# G_R.net
KiCad netlist of a schematic drawn in Altium Designer
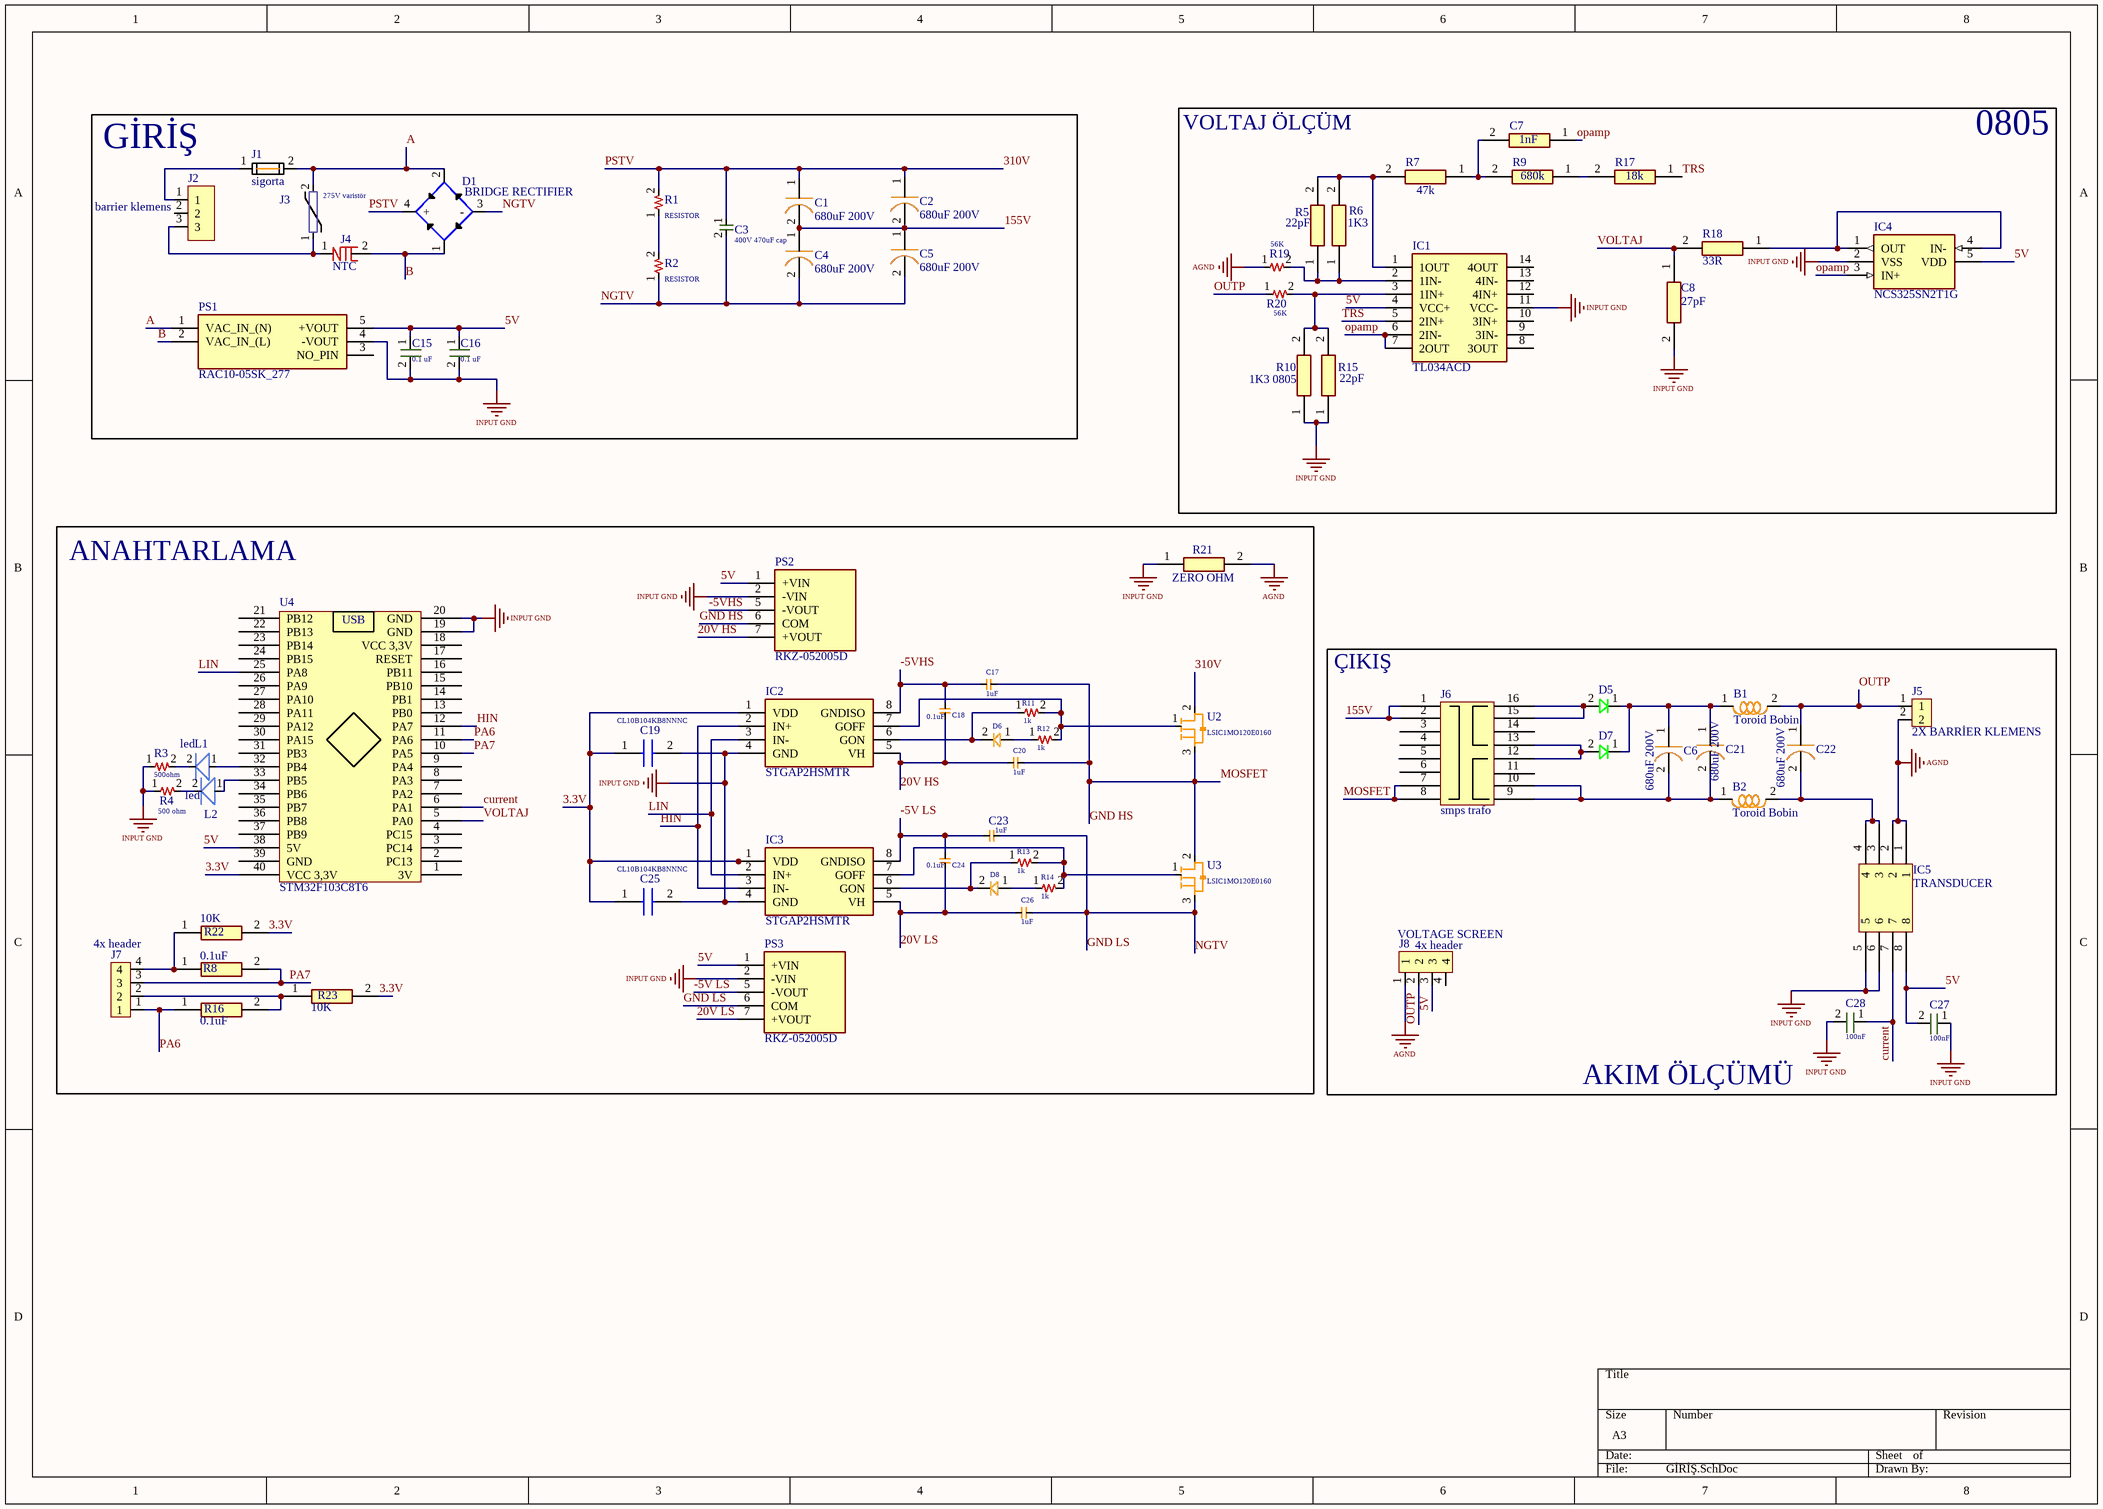
[diagram p0: GİRİŞ.SchDoc]

(export (version "E")
  (design (tool "Eeschema 10.0.6"))
  (components
    (comp (ref "B1")
      (value "Toroid Bobin")
      (footprint "toroid bobin")
      (libsource (lib "Schlib2") (part "Toroid Bobin"))
    )
    (comp (ref "B2")
      (value "Toroid Bobin")
      (footprint "toroid bobin")
      (libsource (lib "Schlib2") (part "Toroid Bobin"))
    )
    (comp (ref "C1")
      (value "680uF 200V")
      (footprint "200v 680uF CAPACITOR")
      (description "CAPACITOR")
      (libsource (lib "Schlib2") (part "680uF 200V"))
    )
    (comp (ref "C2")
      (value "680uF 200V")
      (footprint "200v 680uF CAPACITOR")
      (description "CAPACITOR")
      (libsource (lib "Schlib2") (part "680uF 200V"))
    )
    (comp (ref "C3")
      (value "400V 470uF cap")
      (footprint "400V 470uF")
      (description "470 uF")
      (libsource (lib "Schlib2") (part "400V 470uF cap"))
    )
    (comp (ref "C4")
      (value "680uF 200V")
      (footprint "200v 680uF CAPACITOR")
      (description "CAPACITOR")
      (libsource (lib "Schlib2") (part "680uF 200V"))
    )
    (comp (ref "C5")
      (value "680uF 200V")
      (footprint "200v 680uF CAPACITOR")
      (description "CAPACITOR")
      (libsource (lib "Schlib2") (part "680uF 200V"))
    )
    (comp (ref "C6")
      (value "680uF 200V")
      (footprint "200v 680uF CAPACITOR")
      (description "CAPACITOR")
      (libsource (lib "Schlib2") (part "680uF 200V"))
    )
    (comp (ref "C7")
      (value "1nF")
      (footprint "PcbLib3:RESC2012X65N")
      (description "Resistor")
      (fields
        (field (name "MANUFACTURER_PART_NUMBER") "CPF0805B100RE1")
        (field (name "MOUSER PART NUMBER") "279-CPF0805B100RE1")
      )
      (libsource (lib "") (part "CPF0805B100RE1_3"))
    )
    (comp (ref "C8")
      (value "27pF")
      (footprint "PcbLib3:RESC2012X65N")
      (description "Resistor")
      (fields
        (field (name "MANUFACTURER_PART_NUMBER") "CPF0805B100RE1")
        (field (name "MOUSER PART NUMBER") "279-CPF0805B100RE1")
      )
      (libsource (lib "") (part "CPF0805B100RE1_2"))
    )
    (comp (ref "C15")
      (value "0.1 uF")
      (footprint "0.1 uF mercimek kapasitör")
      (description "CAPACITOR")
      (libsource (lib "Schlib2") (part "0.1 uF mercimek kapasitör"))
    )
    (comp (ref "C16")
      (value "0.1 uF")
      (footprint "0.1 uF mercimek kapasitör")
      (description "CAPACITOR")
      (libsource (lib "Schlib2") (part "0.1 uF mercimek kapasitör"))
    )
    (comp (ref "C17")
      (value "1uF")
      (footprint "KUTU KAPASİTÖR 1uF")
      (libsource (lib "Schlib2") (part "KUTU KAPASİTÖR 1uF"))
    )
    (comp (ref "C18")
      (value "0.1uF")
      (footprint "KUTU KAPASİTÖR 1uF")
      (description "1uF")
      (libsource (lib "Schlib2") (part "KUTU KAPASİTÖR 1uF"))
    )
    (comp (ref "C19")
      (value "CL10B104KB8NNNC")
      (footprint "PcbLib2:CAPC1608X90N")
      (description "Capacitor")
      (fields (field (name "MOUSER PART NUMBER") "187-CL10B104KB8NNNC"))
      (libsource (lib "*") (part "CL10B104KB8NNNC"))
    )
    (comp (ref "C20")
      (value "1uF")
      (footprint "KUTU KAPASİTÖR 1uF")
      (libsource (lib "Schlib2") (part "KUTU KAPASİTÖR 1uF"))
    )
    (comp (ref "C21")
      (value "680uF 200V")
      (footprint "200v 680uF CAPACITOR")
      (description "CAPACITOR")
      (libsource (lib "Schlib2") (part "680uF 200V"))
    )
    (comp (ref "C22")
      (value "680uF 200V")
      (footprint "200v 680uF CAPACITOR")
      (description "CAPACITOR")
      (libsource (lib "Schlib2") (part "680uF 200V"))
    )
    (comp (ref "C23")
      (value "1uF")
      (footprint "KUTU KAPASİTÖR 1uF")
      (libsource (lib "Schlib2") (part "KUTU KAPASİTÖR 1uF"))
    )
    (comp (ref "C24")
      (value "0.1uF")
      (footprint "KUTU KAPASİTÖR 1uF")
      (description "1uF")
      (libsource (lib "Schlib2") (part "KUTU KAPASİTÖR 1uF"))
    )
    (comp (ref "C25")
      (value "CL10B104KB8NNNC")
      (footprint "PcbLib2:CAPC1608X90N")
      (description "Capacitor")
      (fields (field (name "MOUSER PART NUMBER") "187-CL10B104KB8NNNC"))
      (libsource (lib "*") (part "CL10B104KB8NNNC"))
    )
    (comp (ref "C26")
      (value "1uF")
      (footprint "KUTU KAPASİTÖR 1uF")
      (libsource (lib "Schlib2") (part "KUTU KAPASİTÖR 1uF"))
    )
    (comp (ref "C27")
      (value "100nF")
      (footprint "0.1 uF mercimek kapasitör")
      (description "CAPACITOR")
      (libsource (lib "Schlib2") (part "0.1 uF mercimek kapasitör"))
    )
    (comp (ref "C28")
      (value "100nF")
      (footprint "0.1 uF mercimek kapasitör")
      (description "CAPACITOR")
      (libsource (lib "Schlib2") (part "0.1 uF mercimek kapasitör"))
    )
    (comp (ref "D1")
      (value "BRIDGE RECTIFIER")
      (footprint "RECTIFIER")
      (description "RECTIFIER")
      (libsource (lib "Schlib2") (part "BRIDGE RECTIFIER"))
    )
    (comp (ref "D5")
      (value "MUR1560 DIODE")
      (footprint "MUR1560 FAST DIODE")
      (description "DIODE")
      (libsource (lib "Schlib2") (part "MUR1560 DIODE"))
    )
    (comp (ref "D6")
      (value "SF-26 DIODE")
      (footprint "SF-26 DIODE")
      (description "DIODE")
      (libsource (lib "Schlib2") (part "SF-26 DIODE"))
    )
    (comp (ref "D7")
      (value "MUR1560 DIODE")
      (footprint "MUR1560 FAST DIODE")
      (description "DIODE")
      (libsource (lib "Schlib2") (part "MUR1560 DIODE"))
    )
    (comp (ref "D8")
      (value "SF-26 DIODE")
      (footprint "SF-26 DIODE")
      (description "DIODE")
      (libsource (lib "Schlib2") (part "SF-26 DIODE"))
    )
    (comp (ref "IC1")
      (value "TL034ACD")
      (footprint "PcbLib3:SOIC127P600X175-14N")
      (description "Integrated Circuit")
      (fields (field (name "MOUSER PART NUMBER") "595-TL034ACD"))
      (libsource (lib "*") (part "TL034ACD"))
    )
    (comp (ref "IC2")
      (value "STGAP2HSMTR")
      (footprint "PcbLib2:SOIC127P1032X264-8N")
      (description "Integrated Circuit")
      (fields (field (name "MOUSER PART NUMBER") "511-STGAP2HSMTR"))
      (libsource (lib "*") (part "STGAP2HSMTR"))
    )
    (comp (ref "IC3")
      (value "STGAP2HSMTR")
      (footprint "PcbLib2:SOIC127P1032X264-8N")
      (description "Integrated Circuit")
      (fields (field (name "MOUSER PART NUMBER") "511-STGAP2HSMTR"))
      (libsource (lib "*") (part "STGAP2HSMTR"))
    )
    (comp (ref "IC4")
      (value "NCS325SN2T1G")
      (footprint "PcbLib3:SOT95P275X110-5N")
      (description "Integrated Circuit")
      (fields (field (name "MOUSER PART NUMBER") "863-NCS325SN2T1G"))
      (libsource (lib "*") (part "NCS325SN2T1G"))
    )
    (comp (ref "IC5")
      (value "TRANSDUCER")
      (footprint "GHS 16-SME current transducer")
      (libsource (lib "Schlib2") (part "TRANSDUCER"))
    )
    (comp (ref "J1") (value "sigorta") (footprint "FUSE HOLDER") (libsource (lib "Schlib2") (part "sigorta")))
    (comp (ref "J2")
      (value "barrier klemens")
      (footprint "BARRİER KLEMENS")
      (description "9.5mm")
      (libsource (lib "Schlib2") (part "barrier klemens"))
    )
    (comp (ref "J3")
      (value "275V varistör")
      (footprint "Varistor 275V")
      (description "VARISTOR")
      (libsource (lib "Schlib2") (part "275V varistör"))
    )
    (comp (ref "J4")
      (value "NTC")
      (footprint "NTC")
      (description "SİGORTA")
      (libsource (lib "Schlib2") (part "NTC"))
    )
    (comp (ref "J5")
      (value "2X BARRİER KLEMENS")
      (footprint "2X BARRİER KLEMENS")
      (libsource (lib "Schlib2") (part "2X BARRİER KLEMENS"))
    )
    (comp (ref "J6")
      (value "smps trafo")
      (footprint "SMPS TRAFO")
      (libsource (lib "Schlib2") (part "smps trafo"))
    )
    (comp (ref "J7")
      (value "4x header")
      (footprint "4x header")
      (description "header")
      (libsource (lib "") (part "4x header_1"))
    )
    (comp (ref "J8")
      (value "4x header")
      (footprint "4x header")
      (description "header")
      (libsource (lib "Schlib2") (part "4x header"))
    )
    (comp (ref "L1") (value "led") (footprint "led") (libsource (lib "Schlib2") (part "led")))
    (comp (ref "L2") (value "led") (footprint "led") (libsource (lib "Schlib2") (part "led")))
    (comp (ref "PS1")
      (value "RAC10-05SK_277")
      (footprint "PcbLib1:RAC1005SK277")
      (description "Power Supply")
      (fields
        (field (name "MANUFACTURER_PART_NUMBER") "RAC10-05SK/277")
        (field (name "MOUSER PART NUMBER") "919-RAC10-05SK/277")
      )
      (libsource (lib "*") (part "RAC10-05SK_277"))
    )
    (comp (ref "PS2")
      (value "RKZ-052005D")
      (footprint "PcbLib2:RKZ1215SH")
      (description "Power Supply")
      (fields (field (name "MOUSER PART NUMBER") "919-RKZ-052005D"))
      (libsource (lib "*") (part "RKZ-052005D"))
    )
    (comp (ref "PS3")
      (value "RKZ-052005D")
      (footprint "PcbLib2:RKZ1215SH")
      (description "Power Supply")
      (fields (field (name "MOUSER PART NUMBER") "919-RKZ-052005D"))
      (libsource (lib "*") (part "RKZ-052005D"))
    )
    (comp (ref "R1")
      (value "RESISTOR")
      (footprint "GENERAL RESISTOR")
      (description "GENERAL RESISTOR")
      (libsource (lib "Schlib2") (part "RESISTOR"))
    )
    (comp (ref "R2")
      (value "RESISTOR")
      (footprint "GENERAL RESISTOR")
      (description "GENERAL RESISTOR")
      (libsource (lib "Schlib2") (part "RESISTOR"))
    )
    (comp (ref "R3")
      (value "500ohm")
      (footprint "GENERAL RESISTOR")
      (description "GENERAL RESISTOR")
      (libsource (lib "Schlib2") (part "RESISTOR"))
    )
    (comp (ref "R4")
      (value "500 ohm")
      (footprint "GENERAL RESISTOR")
      (description "GENERAL RESISTOR")
      (libsource (lib "Schlib2") (part "RESISTOR"))
    )
    (comp (ref "R5")
      (value "22pF")
      (footprint "PcbLib3:RESC2012X65N")
      (description "Resistor")
      (fields
        (field (name "MANUFACTURER_PART_NUMBER") "CPF0805B100RE1")
        (field (name "MOUSER PART NUMBER") "279-CPF0805B100RE1")
      )
      (libsource (lib "*") (part "CPF0805B100RE1"))
    )
    (comp (ref "R6")
      (value "1K3")
      (footprint "PcbLib3:RESC2012X65N")
      (description "Resistor")
      (fields
        (field (name "MANUFACTURER_PART_NUMBER") "CPF0805B100RE1")
        (field (name "MOUSER PART NUMBER") "279-CPF0805B100RE1")
      )
      (libsource (lib "*") (part "CPF0805B100RE1"))
    )
    (comp (ref "R7")
      (value "47k")
      (footprint "PcbLib3:RESC2012X65N")
      (description "Resistor")
      (fields
        (field (name "MANUFACTURER_PART_NUMBER") "CPF0805B100RE1")
        (field (name "MOUSER PART NUMBER") "279-CPF0805B100RE1")
      )
      (libsource (lib "") (part "CPF0805B100RE1_3"))
    )
    (comp (ref "R8")
      (value "0.1uF")
      (footprint "PcbLib3:RESC2012X65N")
      (description "Resistor")
      (fields
        (field (name "MANUFACTURER_PART_NUMBER") "CPF0805B100RE1")
        (field (name "MOUSER PART NUMBER") "279-CPF0805B100RE1")
      )
      (libsource (lib "") (part "CPF0805B100RE1_1"))
    )
    (comp (ref "R9")
      (value "680k")
      (footprint "PcbLib3:RESC2012X65N")
      (description "Resistor")
      (fields
        (field (name "MANUFACTURER_PART_NUMBER") "CPF0805B100RE1")
        (field (name "MOUSER PART NUMBER") "279-CPF0805B100RE1")
      )
      (libsource (lib "") (part "CPF0805B100RE1_3"))
    )
    (comp (ref "R10")
      (value "1K3 0805")
      (footprint "PcbLib3:RESC2012X65N")
      (description "Resistor")
      (fields
        (field (name "MANUFACTURER_PART_NUMBER") "CPF0805B100RE1")
        (field (name "MOUSER PART NUMBER") "279-CPF0805B100RE1")
      )
      (libsource (lib "*") (part "CPF0805B100RE1"))
    )
    (comp (ref "R11")
      (value "1k")
      (footprint "GENERAL RESISTOR")
      (description "GENERAL RESISTOR")
      (libsource (lib "Schlib2") (part "RESISTOR"))
    )
    (comp (ref "R12")
      (value "1k")
      (footprint "GENERAL RESISTOR")
      (description "GENERAL RESISTOR")
      (libsource (lib "Schlib2") (part "RESISTOR"))
    )
    (comp (ref "R13")
      (value "1k")
      (footprint "GENERAL RESISTOR")
      (description "GENERAL RESISTOR")
      (libsource (lib "Schlib2") (part "RESISTOR"))
    )
    (comp (ref "R14")
      (value "1k")
      (footprint "GENERAL RESISTOR")
      (description "GENERAL RESISTOR")
      (libsource (lib "Schlib2") (part "RESISTOR"))
    )
    (comp (ref "R15")
      (value "22pF")
      (footprint "PcbLib3:RESC2012X65N")
      (description "Resistor")
      (fields
        (field (name "MANUFACTURER_PART_NUMBER") "CPF0805B100RE1")
        (field (name "MOUSER PART NUMBER") "279-CPF0805B100RE1")
      )
      (libsource (lib "*") (part "CPF0805B100RE1"))
    )
    (comp (ref "R16")
      (value "0.1uF")
      (footprint "PcbLib3:RESC2012X65N")
      (description "Resistor")
      (fields
        (field (name "MANUFACTURER_PART_NUMBER") "CPF0805B100RE1")
        (field (name "MOUSER PART NUMBER") "279-CPF0805B100RE1")
      )
      (libsource (lib "") (part "CPF0805B100RE1_1"))
    )
    (comp (ref "R17")
      (value "18k")
      (footprint "PcbLib3:RESC2012X65N")
      (description "Resistor")
      (fields
        (field (name "MANUFACTURER_PART_NUMBER") "CPF0805B100RE1")
        (field (name "MOUSER PART NUMBER") "279-CPF0805B100RE1")
      )
      (libsource (lib "") (part "CPF0805B100RE1_3"))
    )
    (comp (ref "R18")
      (value "33R")
      (footprint "PcbLib3:RESC2012X65N")
      (description "Resistor")
      (fields
        (field (name "MANUFACTURER_PART_NUMBER") "CPF0805B100RE1")
        (field (name "MOUSER PART NUMBER") "279-CPF0805B100RE1")
      )
      (libsource (lib "") (part "CPF0805B100RE1_3"))
    )
    (comp (ref "R19")
      (value "56K")
      (footprint "GENERAL RESISTOR")
      (description "GENERAL RESISTOR")
      (libsource (lib "Schlib2") (part "RESISTOR"))
    )
    (comp (ref "R20")
      (value "56K")
      (footprint "GENERAL RESISTOR")
      (description "GENERAL RESISTOR")
      (libsource (lib "Schlib2") (part "RESISTOR"))
    )
    (comp (ref "R21")
      (value "ZERO OHM")
      (footprint "PcbLib3:RESC3216X75N")
      (description "Resistor")
      (fields
        (field (name "MANUFACTURER_PART_NUMBER") "CR1206-F/-2R00ELF")
        (field (name "MOUSER PART NUMBER") "652-CR1206-F/2R00ELF")
      )
      (libsource (lib "*") (part "CR1206-F_-2R00ELF"))
    )
    (comp (ref "R22")
      (value "10K")
      (footprint "PcbLib3:RESC2012X65N")
      (description "Resistor")
      (fields
        (field (name "MANUFACTURER_PART_NUMBER") "CPF0805B100RE1")
        (field (name "MOUSER PART NUMBER") "279-CPF0805B100RE1")
      )
      (libsource (lib "") (part "CPF0805B100RE1_1"))
    )
    (comp (ref "R23")
      (value "10K")
      (footprint "PcbLib3:RESC2012X65N")
      (description "Resistor")
      (fields
        (field (name "MANUFACTURER_PART_NUMBER") "CPF0805B100RE1")
        (field (name "MOUSER PART NUMBER") "279-CPF0805B100RE1")
      )
      (libsource (lib "") (part "CPF0805B100RE1_1"))
    )
    (comp (ref "U2")
      (value "LSIC1MO120E0160")
      (footprint "LSIC1MO120E0160")
      (description "MOSFET")
      (libsource (lib "Schlib2") (part "LSIC1MO120E0160"))
    )
    (comp (ref "U3")
      (value "LSIC1MO120E0160")
      (footprint "LSIC1MO120E0160")
      (description "MOSFET")
      (libsource (lib "Schlib2") (part "LSIC1MO120E0160"))
    )
    (comp (ref "U4")
      (value "STM32F103C8T6")
      (footprint "STM32 BLUE PİLL")
      (description "CONTROLLER")
      (libsource (lib "Schlib2") (part "stm32 blue pill"))
    )
  )
  (nets
    (net (code "1") (name "/-5V LS") (class "Default")
      (node (ref "C23") (pin "1") (pinfunction "1_1") (pintype "passive"))
      (node (ref "C24") (pin "1") (pinfunction "1_1") (pintype "passive"))
      (node (ref "IC3") (pin "8") (pinfunction "GNDISO_8") (pintype "passive"))
      (node (ref "PS3") (pin "5") (pinfunction "-VOUT_5") (pintype "passive"))
    )
    (net (code "2") (name "/-5VHS") (class "Default")
      (node (ref "C17") (pin "1") (pinfunction "1_1") (pintype "passive"))
      (node (ref "C18") (pin "1") (pinfunction "1_1") (pintype "passive"))
      (node (ref "IC2") (pin "8") (pinfunction "GNDISO_8") (pintype "passive"))
      (node (ref "PS2") (pin "5") (pinfunction "-VOUT_5") (pintype "passive"))
    )
    (net (code "3") (name "/3.3V") (class "Default")
      (node (ref "C19") (pin "1") (pinfunction "1_1") (pintype "passive"))
      (node (ref "C25") (pin "1") (pinfunction "1_1") (pintype "passive"))
      (node (ref "IC2") (pin "1") (pinfunction "VDD_1") (pintype "passive"))
      (node (ref "IC3") (pin "1") (pinfunction "VDD_1") (pintype "passive"))
      (node (ref "R22") (pin "2") (pinfunction "2_2") (pintype "passive"))
      (node (ref "R23") (pin "2") (pinfunction "2_2") (pintype "passive"))
      (node (ref "U4") (pin "40") (pinfunction "VCC_3,3V_40") (pintype "passive"))
    )
    (net (code "4") (name "/5V") (class "Default")
      (node (ref "C15") (pin "1") (pinfunction "1_1") (pintype "passive"))
      (node (ref "C16") (pin "1") (pinfunction "1_1") (pintype "passive"))
      (node (ref "C27") (pin "2") (pinfunction "2_2") (pintype "passive"))
      (node (ref "IC1") (pin "4") (pinfunction "VCC+_4") (pintype "passive"))
      (node (ref "IC4") (pin "5") (pinfunction "VDD_5") (pintype "power_in"))
      (node (ref "IC5") (pin "8") (pinfunction "8_8") (pintype "passive"))
      (node (ref "J8") (pin "3") (pinfunction "3_3") (pintype "passive"))
      (node (ref "PS1") (pin "5") (pinfunction "+VOUT_5") (pintype "passive"))
      (node (ref "PS2") (pin "1") (pinfunction "+VIN_1") (pintype "passive"))
      (node (ref "PS3") (pin "1") (pinfunction "+VIN_1") (pintype "passive"))
      (node (ref "U4") (pin "38") (pinfunction "5V_38") (pintype "passive"))
    )
    (net (code "5") (name "/20V HS") (class "Default")
      (node (ref "C18") (pin "2") (pinfunction "2_2") (pintype "passive"))
      (node (ref "C20") (pin "1") (pinfunction "1_1") (pintype "passive"))
      (node (ref "IC2") (pin "5") (pinfunction "VH_5") (pintype "passive"))
      (node (ref "PS2") (pin "7") (pinfunction "+VOUT_7") (pintype "passive"))
    )
    (net (code "6") (name "/20V LS") (class "Default")
      (node (ref "C24") (pin "2") (pinfunction "2_2") (pintype "passive"))
      (node (ref "C26") (pin "1") (pinfunction "1_1") (pintype "passive"))
      (node (ref "IC3") (pin "5") (pinfunction "VH_5") (pintype "passive"))
      (node (ref "PS3") (pin "7") (pinfunction "+VOUT_7") (pintype "passive"))
    )
    (net (code "7") (name "/155V") (class "Default")
      (node (ref "C1") (pin "2") (pinfunction "2_2") (pintype "passive"))
      (node (ref "C2") (pin "2") (pinfunction "2_2") (pintype "passive"))
      (node (ref "C4") (pin "1") (pinfunction "1_1") (pintype "passive"))
      (node (ref "C5") (pin "1") (pinfunction "1_1") (pintype "passive"))
      (node (ref "J6") (pin "1") (pinfunction "1_1") (pintype "passive"))
      (node (ref "J6") (pin "2") (pinfunction "2_2") (pintype "passive"))
    )
    (net (code "8") (name "/310V") (class "Default")
      (node (ref "C1") (pin "1") (pinfunction "1_1") (pintype "passive"))
      (node (ref "C2") (pin "1") (pinfunction "1_1") (pintype "passive"))
      (node (ref "C3") (pin "1") (pinfunction "1_1") (pintype "passive"))
      (node (ref "D1") (pin "4") (pinfunction "+_4") (pintype "passive"))
      (node (ref "R1") (pin "2") (pinfunction "2_2") (pintype "passive"))
      (node (ref "U2") (pin "2") (pinfunction "D_2") (pintype "passive"))
    )
    (net (code "9") (name "/A") (class "Default")
      (node (ref "D1") (pin "2") (pinfunction "2_2") (pintype "passive"))
      (node (ref "J1") (pin "2") (pinfunction "2_2") (pintype "passive"))
      (node (ref "J3") (pin "2") (pinfunction "2_2") (pintype "passive"))
      (node (ref "PS1") (pin "1") (pinfunction "VAC_IN_(N)_1") (pintype "passive"))
    )
    (net (code "10") (name "/B") (class "Default")
      (node (ref "D1") (pin "1") (pinfunction "1_1") (pintype "passive"))
      (node (ref "J4") (pin "2") (pinfunction "2_2") (pintype "passive"))
      (node (ref "PS1") (pin "2") (pinfunction "VAC_IN_(L)_2") (pintype "passive"))
    )
    (net (code "11") (name "/GND HS") (class "Default")
      (node (ref "C17") (pin "2") (pinfunction "2_2") (pintype "passive"))
      (node (ref "C20") (pin "2") (pinfunction "2_2") (pintype "passive"))
      (node (ref "J6") (pin "7") (pinfunction "7_7") (pintype "passive"))
      (node (ref "J6") (pin "8") (pinfunction "8_8") (pintype "passive"))
      (node (ref "PS2") (pin "6") (pinfunction "COM_6") (pintype "passive"))
      (node (ref "U2") (pin "3") (pinfunction "S_3") (pintype "passive"))
      (node (ref "U3") (pin "2") (pinfunction "D_2") (pintype "passive"))
    )
    (net (code "12") (name "/GND LS") (class "Default")
      (node (ref "C23") (pin "2") (pinfunction "2_2") (pintype "passive"))
      (node (ref "C26") (pin "2") (pinfunction "2_2") (pintype "passive"))
      (node (ref "C3") (pin "2") (pinfunction "2_2") (pintype "passive"))
      (node (ref "C4") (pin "2") (pinfunction "2_2") (pintype "passive"))
      (node (ref "C5") (pin "2") (pinfunction "2_2") (pintype "passive"))
      (node (ref "D1") (pin "3") (pinfunction "-_3") (pintype "passive"))
      (node (ref "PS3") (pin "6") (pinfunction "COM_6") (pintype "passive"))
      (node (ref "R2") (pin "1") (pinfunction "1_1") (pintype "passive"))
      (node (ref "U3") (pin "3") (pinfunction "S_3") (pintype "passive"))
    )
    (net (code "13") (name "/HIN") (class "Default")
      (node (ref "IC2") (pin "2") (pinfunction "IN+_2") (pintype "passive"))
      (node (ref "IC3") (pin "3") (pinfunction "IN-_3") (pintype "passive"))
      (node (ref "U4") (pin "12") (pinfunction "PA7_12") (pintype "passive"))
    )
    (net (code "14") (name "/LIN") (class "Default")
      (node (ref "IC2") (pin "3") (pinfunction "IN-_3") (pintype "passive"))
      (node (ref "IC3") (pin "2") (pinfunction "IN+_2") (pintype "passive"))
      (node (ref "U4") (pin "25") (pinfunction "PA8_25") (pintype "passive"))
    )
    (net (code "15") (name "/OUTP") (class "Default")
      (node (ref "B1") (pin "2") (pinfunction "2_2") (pintype "passive"))
      (node (ref "C22") (pin "1") (pinfunction "1_1") (pintype "passive"))
      (node (ref "J5") (pin "1") (pinfunction "1_1") (pintype "passive"))
      (node (ref "J8") (pin "2") (pinfunction "2_2") (pintype "passive"))
      (node (ref "R20") (pin "1") (pinfunction "1_1") (pintype "passive"))
    )
    (net (code "16") (name "/PA6") (class "Default")
      (node (ref "J7") (pin "1") (pinfunction "1_1") (pintype "passive"))
      (node (ref "R16") (pin "1") (pinfunction "1_1") (pintype "passive"))
      (node (ref "U4") (pin "11") (pinfunction "PA6_11") (pintype "passive"))
    )
    (net (code "17") (name "/PA7") (class "Default")
      (node (ref "J7") (pin "3") (pinfunction "3_3") (pintype "passive"))
      (node (ref "R8") (pin "2") (pinfunction "2_2") (pintype "passive"))
      (node (ref "U4") (pin "10") (pinfunction "PA5_10") (pintype "passive"))
    )
    (net (code "18") (name "/TRS") (class "Default")
      (node (ref "IC1") (pin "5") (pinfunction "2IN+_5") (pintype "passive"))
      (node (ref "R17") (pin "1") (pinfunction "1_1") (pintype "passive"))
    )
    (net (code "19") (name "/VOLTAJ") (class "Default")
      (node (ref "C8") (pin "1") (pinfunction "1_1") (pintype "passive"))
      (node (ref "R18") (pin "2") (pinfunction "2_2") (pintype "passive"))
      (node (ref "U4") (pin "5") (pinfunction "PA0_5") (pintype "passive"))
    )
    (net (code "20") (name "/current") (class "Default")
      (node (ref "C28") (pin "1") (pinfunction "1_1") (pintype "passive"))
      (node (ref "IC5") (pin "7") (pinfunction "7_7") (pintype "passive"))
      (node (ref "U4") (pin "6") (pinfunction "PA1_6") (pintype "passive"))
    )
    (net (code "21") (name "/opamp") (class "Default")
      (node (ref "C7") (pin "1") (pinfunction "1_1") (pintype "passive"))
      (node (ref "IC1") (pin "6") (pinfunction "2IN-_6") (pintype "passive"))
      (node (ref "IC1") (pin "7") (pinfunction "2OUT_7") (pintype "passive"))
      (node (ref "IC4") (pin "3") (pinfunction "IN+_3") (pintype "input"))
    )
    (net (code "22") (name "AGND") (class "Default")
      (node (ref "IC5") (pin "1") (pinfunction "1_1") (pintype "passive"))
      (node (ref "IC5") (pin "2") (pinfunction "2_2") (pintype "passive"))
      (node (ref "J5") (pin "2") (pinfunction "2_2") (pintype "passive"))
      (node (ref "J8") (pin "1") (pinfunction "1_1") (pintype "passive"))
      (node (ref "R19") (pin "1") (pinfunction "1_1") (pintype "passive"))
      (node (ref "R21") (pin "2") (pinfunction "2_2") (pintype "passive"))
    )
    (net (code "23") (name "INPUT GND") (class "Default")
      (node (ref "C15") (pin "2") (pinfunction "2_2") (pintype "passive"))
      (node (ref "C16") (pin "2") (pinfunction "2_2") (pintype "passive"))
      (node (ref "C19") (pin "2") (pinfunction "2_2") (pintype "passive"))
      (node (ref "C25") (pin "2") (pinfunction "2_2") (pintype "passive"))
      (node (ref "C27") (pin "1") (pinfunction "1_1") (pintype "passive"))
      (node (ref "C28") (pin "2") (pinfunction "2_2") (pintype "passive"))
      (node (ref "C8") (pin "2") (pinfunction "2_2") (pintype "passive"))
      (node (ref "IC1") (pin "11") (pinfunction "VCC-_11") (pintype "passive"))
      (node (ref "IC2") (pin "4") (pinfunction "GND_4") (pintype "passive"))
      (node (ref "IC3") (pin "4") (pinfunction "GND_4") (pintype "passive"))
      (node (ref "IC4") (pin "2") (pinfunction "VSS_2") (pintype "power_in"))
      (node (ref "IC5") (pin "5") (pinfunction "5_5") (pintype "passive"))
      (node (ref "IC5") (pin "6") (pinfunction "6_6") (pintype "passive"))
      (node (ref "PS1") (pin "4") (pinfunction "-VOUT_4") (pintype "passive"))
      (node (ref "PS2") (pin "2") (pinfunction "-VIN_2") (pintype "passive"))
      (node (ref "PS3") (pin "2") (pinfunction "-VIN_2") (pintype "passive"))
      (node (ref "R10") (pin "1") (pinfunction "1_1") (pintype "passive"))
      (node (ref "R15") (pin "1") (pinfunction "1_1") (pintype "passive"))
      (node (ref "R21") (pin "1") (pinfunction "1_1") (pintype "passive"))
      (node (ref "R3") (pin "1") (pinfunction "1_1") (pintype "passive"))
      (node (ref "R4") (pin "1") (pinfunction "1_1") (pintype "passive"))
      (node (ref "U4") (pin "19") (pinfunction "GND_19") (pintype "passive"))
      (node (ref "U4") (pin "20") (pinfunction "GND_20") (pintype "passive"))
    )
    (net (code "24") (name "Net-(B2-Pad1)") (class "Default")
      (node (ref "B2") (pin "1") (pinfunction "1_1") (pintype "passive"))
      (node (ref "C21") (pin "2") (pinfunction "2_2") (pintype "passive"))
      (node (ref "C6") (pin "2") (pinfunction "2_2") (pintype "passive"))
      (node (ref "J6") (pin "10") (pinfunction "10_10") (pintype "passive"))
      (node (ref "J6") (pin "9") (pinfunction "9_9") (pintype "passive"))
    )
    (net (code "25") (name "Net-(B2-Pad2)") (class "Default")
      (node (ref "B2") (pin "2") (pinfunction "2_2") (pintype "passive"))
      (node (ref "C22") (pin "2") (pinfunction "2_2") (pintype "passive"))
      (node (ref "IC5") (pin "3") (pinfunction "3_3") (pintype "passive"))
      (node (ref "IC5") (pin "4") (pinfunction "4_4") (pintype "passive"))
    )
    (net (code "26") (name "Net-(C7-Pad2)") (class "Default")
      (node (ref "C7") (pin "2") (pinfunction "2_2") (pintype "passive"))
      (node (ref "R7") (pin "1") (pinfunction "1_1") (pintype "passive"))
      (node (ref "R9") (pin "2") (pinfunction "2_2") (pintype "passive"))
    )
    (net (code "27") (name "Net-(D5-3)") (class "Default")
      (node (ref "D5") (pin "2") (pinfunction "3_2") (pintype "passive"))
      (node (ref "J6") (pin "15") (pinfunction "15_15") (pintype "passive"))
      (node (ref "J6") (pin "16") (pinfunction "16_16") (pintype "passive"))
    )
    (net (code "28") (name "Net-(D5-4)") (class "Default")
      (node (ref "B1") (pin "1") (pinfunction "1_1") (pintype "passive"))
      (node (ref "C21") (pin "1") (pinfunction "1_1") (pintype "passive"))
      (node (ref "C6") (pin "1") (pinfunction "1_1") (pintype "passive"))
      (node (ref "D5") (pin "1") (pinfunction "4_1") (pintype "passive"))
      (node (ref "D7") (pin "1") (pinfunction "4_1") (pintype "passive"))
    )
    (net (code "29") (name "Net-(D6-Pad1)") (class "Default")
      (node (ref "D6") (pin "1") (pinfunction "1_1") (pintype "passive"))
      (node (ref "R12") (pin "1") (pinfunction "1_1") (pintype "passive"))
    )
    (net (code "30") (name "Net-(D7-3)") (class "Default")
      (node (ref "D7") (pin "2") (pinfunction "3_2") (pintype "passive"))
      (node (ref "J6") (pin "12") (pinfunction "12_12") (pintype "passive"))
      (node (ref "J6") (pin "13") (pinfunction "13_13") (pintype "passive"))
    )
    (net (code "31") (name "Net-(D8-Pad1)") (class "Default")
      (node (ref "D8") (pin "1") (pinfunction "1_1") (pintype "passive"))
      (node (ref "R14") (pin "1") (pinfunction "1_1") (pintype "passive"))
    )
    (net (code "32") (name "Net-(IC1-1IN+)") (class "Default")
      (node (ref "IC1") (pin "3") (pinfunction "1IN+_3") (pintype "passive"))
      (node (ref "R10") (pin "2") (pinfunction "2_2") (pintype "passive"))
      (node (ref "R15") (pin "2") (pinfunction "2_2") (pintype "passive"))
      (node (ref "R20") (pin "2") (pinfunction "2_2") (pintype "passive"))
    )
    (net (code "33") (name "Net-(IC1-1IN-)") (class "Default")
      (node (ref "IC1") (pin "2") (pinfunction "1IN-_2") (pintype "passive"))
      (node (ref "R19") (pin "2") (pinfunction "2_2") (pintype "passive"))
      (node (ref "R5") (pin "1") (pinfunction "1_1") (pintype "passive"))
      (node (ref "R6") (pin "1") (pinfunction "1_1") (pintype "passive"))
    )
    (net (code "34") (name "Net-(IC1-1OUT)") (class "Default")
      (node (ref "IC1") (pin "1") (pinfunction "1OUT_1") (pintype "passive"))
      (node (ref "R5") (pin "2") (pinfunction "2_2") (pintype "passive"))
      (node (ref "R6") (pin "2") (pinfunction "2_2") (pintype "passive"))
      (node (ref "R7") (pin "2") (pinfunction "2_2") (pintype "passive"))
    )
    (net (code "35") (name "Net-(IC2-GOFF)") (class "Default")
      (node (ref "IC2") (pin "7") (pinfunction "GOFF_7") (pintype "passive"))
      (node (ref "R11") (pin "2") (pinfunction "2_2") (pintype "passive"))
      (node (ref "R12") (pin "2") (pinfunction "2_2") (pintype "passive"))
      (node (ref "U2") (pin "1") (pinfunction "G_1") (pintype "passive"))
    )
    (net (code "36") (name "Net-(IC2-GON)") (class "Default")
      (node (ref "D6") (pin "2") (pinfunction "2_2") (pintype "passive"))
      (node (ref "IC2") (pin "6") (pinfunction "GON_6") (pintype "passive"))
      (node (ref "R11") (pin "1") (pinfunction "1_1") (pintype "passive"))
    )
    (net (code "37") (name "Net-(IC3-GOFF)") (class "Default")
      (node (ref "IC3") (pin "7") (pinfunction "GOFF_7") (pintype "passive"))
      (node (ref "R13") (pin "2") (pinfunction "2_2") (pintype "passive"))
      (node (ref "R14") (pin "2") (pinfunction "2_2") (pintype "passive"))
      (node (ref "U3") (pin "1") (pinfunction "G_1") (pintype "passive"))
    )
    (net (code "38") (name "Net-(IC3-GON)") (class "Default")
      (node (ref "D8") (pin "2") (pinfunction "2_2") (pintype "passive"))
      (node (ref "IC3") (pin "6") (pinfunction "GON_6") (pintype "passive"))
      (node (ref "R13") (pin "1") (pinfunction "1_1") (pintype "passive"))
    )
    (net (code "39") (name "Net-(IC4-IN-)") (class "Default")
      (node (ref "IC4") (pin "1") (pinfunction "OUT_1") (pintype "output"))
      (node (ref "IC4") (pin "4") (pinfunction "IN-_4") (pintype "input"))
      (node (ref "R18") (pin "1") (pinfunction "1_1") (pintype "passive"))
    )
    (net (code "40") (name "Net-(J1-Pad1)") (class "Default")
      (node (ref "J1") (pin "1") (pinfunction "1_1") (pintype "passive"))
      (node (ref "J2") (pin "1") (pinfunction "1_1") (pintype "passive"))
    )
    (net (code "41") (name "Net-(J2-Pad3)") (class "Default")
      (node (ref "J2") (pin "3") (pinfunction "3_3") (pintype "passive"))
      (node (ref "J3") (pin "1") (pinfunction "1_1") (pintype "passive"))
      (node (ref "J4") (pin "1") (pinfunction "1_1") (pintype "passive"))
    )
    (net (code "42") (name "Net-(J7-Pad2)") (class "Default")
      (node (ref "J7") (pin "2") (pinfunction "2_2") (pintype "passive"))
      (node (ref "R16") (pin "2") (pinfunction "2_2") (pintype "passive"))
      (node (ref "R23") (pin "1") (pinfunction "1_1") (pintype "passive"))
    )
    (net (code "43") (name "Net-(J7-Pad4)") (class "Default")
      (node (ref "J7") (pin "4") (pinfunction "4_4") (pintype "passive"))
      (node (ref "R22") (pin "1") (pinfunction "1_1") (pintype "passive"))
      (node (ref "R8") (pin "1") (pinfunction "1_1") (pintype "passive"))
    )
    (net (code "44") (name "Net-(L1-5)") (class "Default")
      (node (ref "L1") (pin "1") (pinfunction "5_1") (pintype "passive"))
      (node (ref "U4") (pin "32") (pinfunction "PB4_32") (pintype "passive"))
    )
    (net (code "45") (name "Net-(L1-6)") (class "Default")
      (node (ref "L1") (pin "2") (pinfunction "6_2") (pintype "passive"))
      (node (ref "R3") (pin "2") (pinfunction "2_2") (pintype "passive"))
    )
    (net (code "46") (name "Net-(L2-5)") (class "Default")
      (node (ref "L2") (pin "1") (pinfunction "5_1") (pintype "passive"))
      (node (ref "U4") (pin "33") (pinfunction "PB5_33") (pintype "passive"))
    )
    (net (code "47") (name "Net-(L2-6)") (class "Default")
      (node (ref "L2") (pin "2") (pinfunction "6_2") (pintype "passive"))
      (node (ref "R4") (pin "2") (pinfunction "2_2") (pintype "passive"))
    )
    (net (code "48") (name "Net-(R1-Pad1)") (class "Default")
      (node (ref "R1") (pin "1") (pinfunction "1_1") (pintype "passive"))
      (node (ref "R2") (pin "2") (pinfunction "2_2") (pintype "passive"))
    )
    (net (code "49") (name "Net-(R17-Pad2)") (class "Default")
      (node (ref "R17") (pin "2") (pinfunction "2_2") (pintype "passive"))
      (node (ref "R9") (pin "1") (pinfunction "1_1") (pintype "passive"))
    )
    (net (code "50") (name "unconnected-(IC1-3IN+-Pad10)") (class "Default")
      (node (ref "IC1") (pin "10") (pinfunction "3IN+_10") (pintype "passive"))
    )
    (net (code "51") (name "unconnected-(IC1-3IN--Pad9)") (class "Default")
      (node (ref "IC1") (pin "9") (pinfunction "3IN-_9") (pintype "passive"))
    )
    (net (code "52") (name "unconnected-(IC1-3OUT-Pad8)") (class "Default")
      (node (ref "IC1") (pin "8") (pinfunction "3OUT_8") (pintype "passive"))
    )
    (net (code "53") (name "unconnected-(IC1-4IN+-Pad12)") (class "Default")
      (node (ref "IC1") (pin "12") (pinfunction "4IN+_12") (pintype "passive"))
    )
    (net (code "54") (name "unconnected-(IC1-4IN--Pad13)") (class "Default")
      (node (ref "IC1") (pin "13") (pinfunction "4IN-_13") (pintype "passive"))
    )
    (net (code "55") (name "unconnected-(IC1-4OUT-Pad14)") (class "Default")
      (node (ref "IC1") (pin "14") (pinfunction "4OUT_14") (pintype "passive"))
    )
    (net (code "56") (name "unconnected-(J2-Pad2)") (class "Default")
      (node (ref "J2") (pin "2") (pinfunction "2_2") (pintype "passive"))
    )
    (net (code "57") (name "unconnected-(J6-Pad3)") (class "Default")
      (node (ref "J6") (pin "3") (pinfunction "3_3") (pintype "passive"))
    )
    (net (code "58") (name "unconnected-(J6-Pad4)") (class "Default")
      (node (ref "J6") (pin "4") (pinfunction "4_4") (pintype "passive"))
    )
    (net (code "59") (name "unconnected-(J6-Pad5)") (class "Default")
      (node (ref "J6") (pin "5") (pinfunction "5_5") (pintype "passive"))
    )
    (net (code "60") (name "unconnected-(J6-Pad6)") (class "Default")
      (node (ref "J6") (pin "6") (pinfunction "6_6") (pintype "passive"))
    )
    (net (code "61") (name "unconnected-(J6-Pad11)") (class "Default")
      (node (ref "J6") (pin "11") (pinfunction "11_11") (pintype "passive"))
    )
    (net (code "62") (name "unconnected-(J6-Pad14)") (class "Default")
      (node (ref "J6") (pin "14") (pinfunction "14_14") (pintype "passive"))
    )
    (net (code "63") (name "unconnected-(J8-Pad4)") (class "Default")
      (node (ref "J8") (pin "4") (pinfunction "4_4") (pintype "passive"))
    )
    (net (code "64") (name "unconnected-(PS1-NO_PIN-Pad3)") (class "Default")
      (node (ref "PS1") (pin "3") (pinfunction "NO_PIN_3") (pintype "passive"))
    )
    (net (code "65") (name "unconnected-(U4-3V-Pad1)") (class "Default")
      (node (ref "U4") (pin "1") (pinfunction "3V_1") (pintype "passive"))
    )
    (net (code "66") (name "unconnected-(U4-GND-Pad39)") (class "Default")
      (node (ref "U4") (pin "39") (pinfunction "GND_39") (pintype "passive"))
    )
    (net (code "67") (name "unconnected-(U4-PA2-Pad7)") (class "Default")
      (node (ref "U4") (pin "7") (pinfunction "PA2_7") (pintype "passive"))
    )
    (net (code "68") (name "unconnected-(U4-PA3-Pad8)") (class "Default")
      (node (ref "U4") (pin "8") (pinfunction "PA3_8") (pintype "passive"))
    )
    (net (code "69") (name "unconnected-(U4-PA4-Pad9)") (class "Default")
      (node (ref "U4") (pin "9") (pinfunction "PA4_9") (pintype "passive"))
    )
    (net (code "70") (name "unconnected-(U4-PA9-Pad26)") (class "Default")
      (node (ref "U4") (pin "26") (pinfunction "PA9_26") (pintype "passive"))
    )
    (net (code "71") (name "unconnected-(U4-PA10-Pad27)") (class "Default")
      (node (ref "U4") (pin "27") (pinfunction "PA10_27") (pintype "passive"))
    )
    (net (code "72") (name "unconnected-(U4-PA11-Pad28)") (class "Default")
      (node (ref "U4") (pin "28") (pinfunction "PA11_28") (pintype "passive"))
    )
    (net (code "73") (name "unconnected-(U4-PA12-Pad29)") (class "Default")
      (node (ref "U4") (pin "29") (pinfunction "PA12_29") (pintype "passive"))
    )
    (net (code "74") (name "unconnected-(U4-PA15-Pad30)") (class "Default")
      (node (ref "U4") (pin "30") (pinfunction "PA15_30") (pintype "passive"))
    )
    (net (code "75") (name "unconnected-(U4-PB0-Pad13)") (class "Default")
      (node (ref "U4") (pin "13") (pinfunction "PB0_13") (pintype "passive"))
    )
    (net (code "76") (name "unconnected-(U4-PB1-Pad14)") (class "Default")
      (node (ref "U4") (pin "14") (pinfunction "PB1_14") (pintype "passive"))
    )
    (net (code "77") (name "unconnected-(U4-PB3-Pad31)") (class "Default")
      (node (ref "U4") (pin "31") (pinfunction "PB3_31") (pintype "passive"))
    )
    (net (code "78") (name "unconnected-(U4-PB6-Pad34)") (class "Default")
      (node (ref "U4") (pin "34") (pinfunction "PB6_34") (pintype "passive"))
    )
    (net (code "79") (name "unconnected-(U4-PB7-Pad35)") (class "Default")
      (node (ref "U4") (pin "35") (pinfunction "PB7_35") (pintype "passive"))
    )
    (net (code "80") (name "unconnected-(U4-PB8-Pad36)") (class "Default")
      (node (ref "U4") (pin "36") (pinfunction "PB8_36") (pintype "passive"))
    )
    (net (code "81") (name "unconnected-(U4-PB9-Pad37)") (class "Default")
      (node (ref "U4") (pin "37") (pinfunction "PB9_37") (pintype "passive"))
    )
    (net (code "82") (name "unconnected-(U4-PB10-Pad15)") (class "Default")
      (node (ref "U4") (pin "15") (pinfunction "PB10_15") (pintype "passive"))
    )
    (net (code "83") (name "unconnected-(U4-PB11-Pad16)") (class "Default")
      (node (ref "U4") (pin "16") (pinfunction "PB11_16") (pintype "passive"))
    )
    (net (code "84") (name "unconnected-(U4-PB12-Pad21)") (class "Default")
      (node (ref "U4") (pin "21") (pinfunction "PB12_21") (pintype "passive"))
    )
    (net (code "85") (name "unconnected-(U4-PB13-Pad22)") (class "Default")
      (node (ref "U4") (pin "22") (pinfunction "PB13_22") (pintype "passive"))
    )
    (net (code "86") (name "unconnected-(U4-PB14-Pad23)") (class "Default")
      (node (ref "U4") (pin "23") (pinfunction "PB14_23") (pintype "passive"))
    )
    (net (code "87") (name "unconnected-(U4-PB15-Pad24)") (class "Default")
      (node (ref "U4") (pin "24") (pinfunction "PB15_24") (pintype "passive"))
    )
    (net (code "88") (name "unconnected-(U4-PC13-Pad2)") (class "Default")
      (node (ref "U4") (pin "2") (pinfunction "PC13_2") (pintype "passive"))
    )
    (net (code "89") (name "unconnected-(U4-PC14-Pad3)") (class "Default")
      (node (ref "U4") (pin "3") (pinfunction "PC14_3") (pintype "passive"))
    )
    (net (code "90") (name "unconnected-(U4-PC15-Pad4)") (class "Default")
      (node (ref "U4") (pin "4") (pinfunction "PC15_4") (pintype "passive"))
    )
    (net (code "91") (name "unconnected-(U4-RESET-Pad17)") (class "Default")
      (node (ref "U4") (pin "17") (pinfunction "RESET_17") (pintype "passive"))
    )
    (net (code "92") (name "unconnected-(U4-VCC_3,3V-Pad18)") (class "Default")
      (node (ref "U4") (pin "18") (pinfunction "VCC_3,3V_18") (pintype "passive"))
    )
  )
)
